# FPGA_14_15.net
KiCad netlist of a schematic drawn in Altium Designer
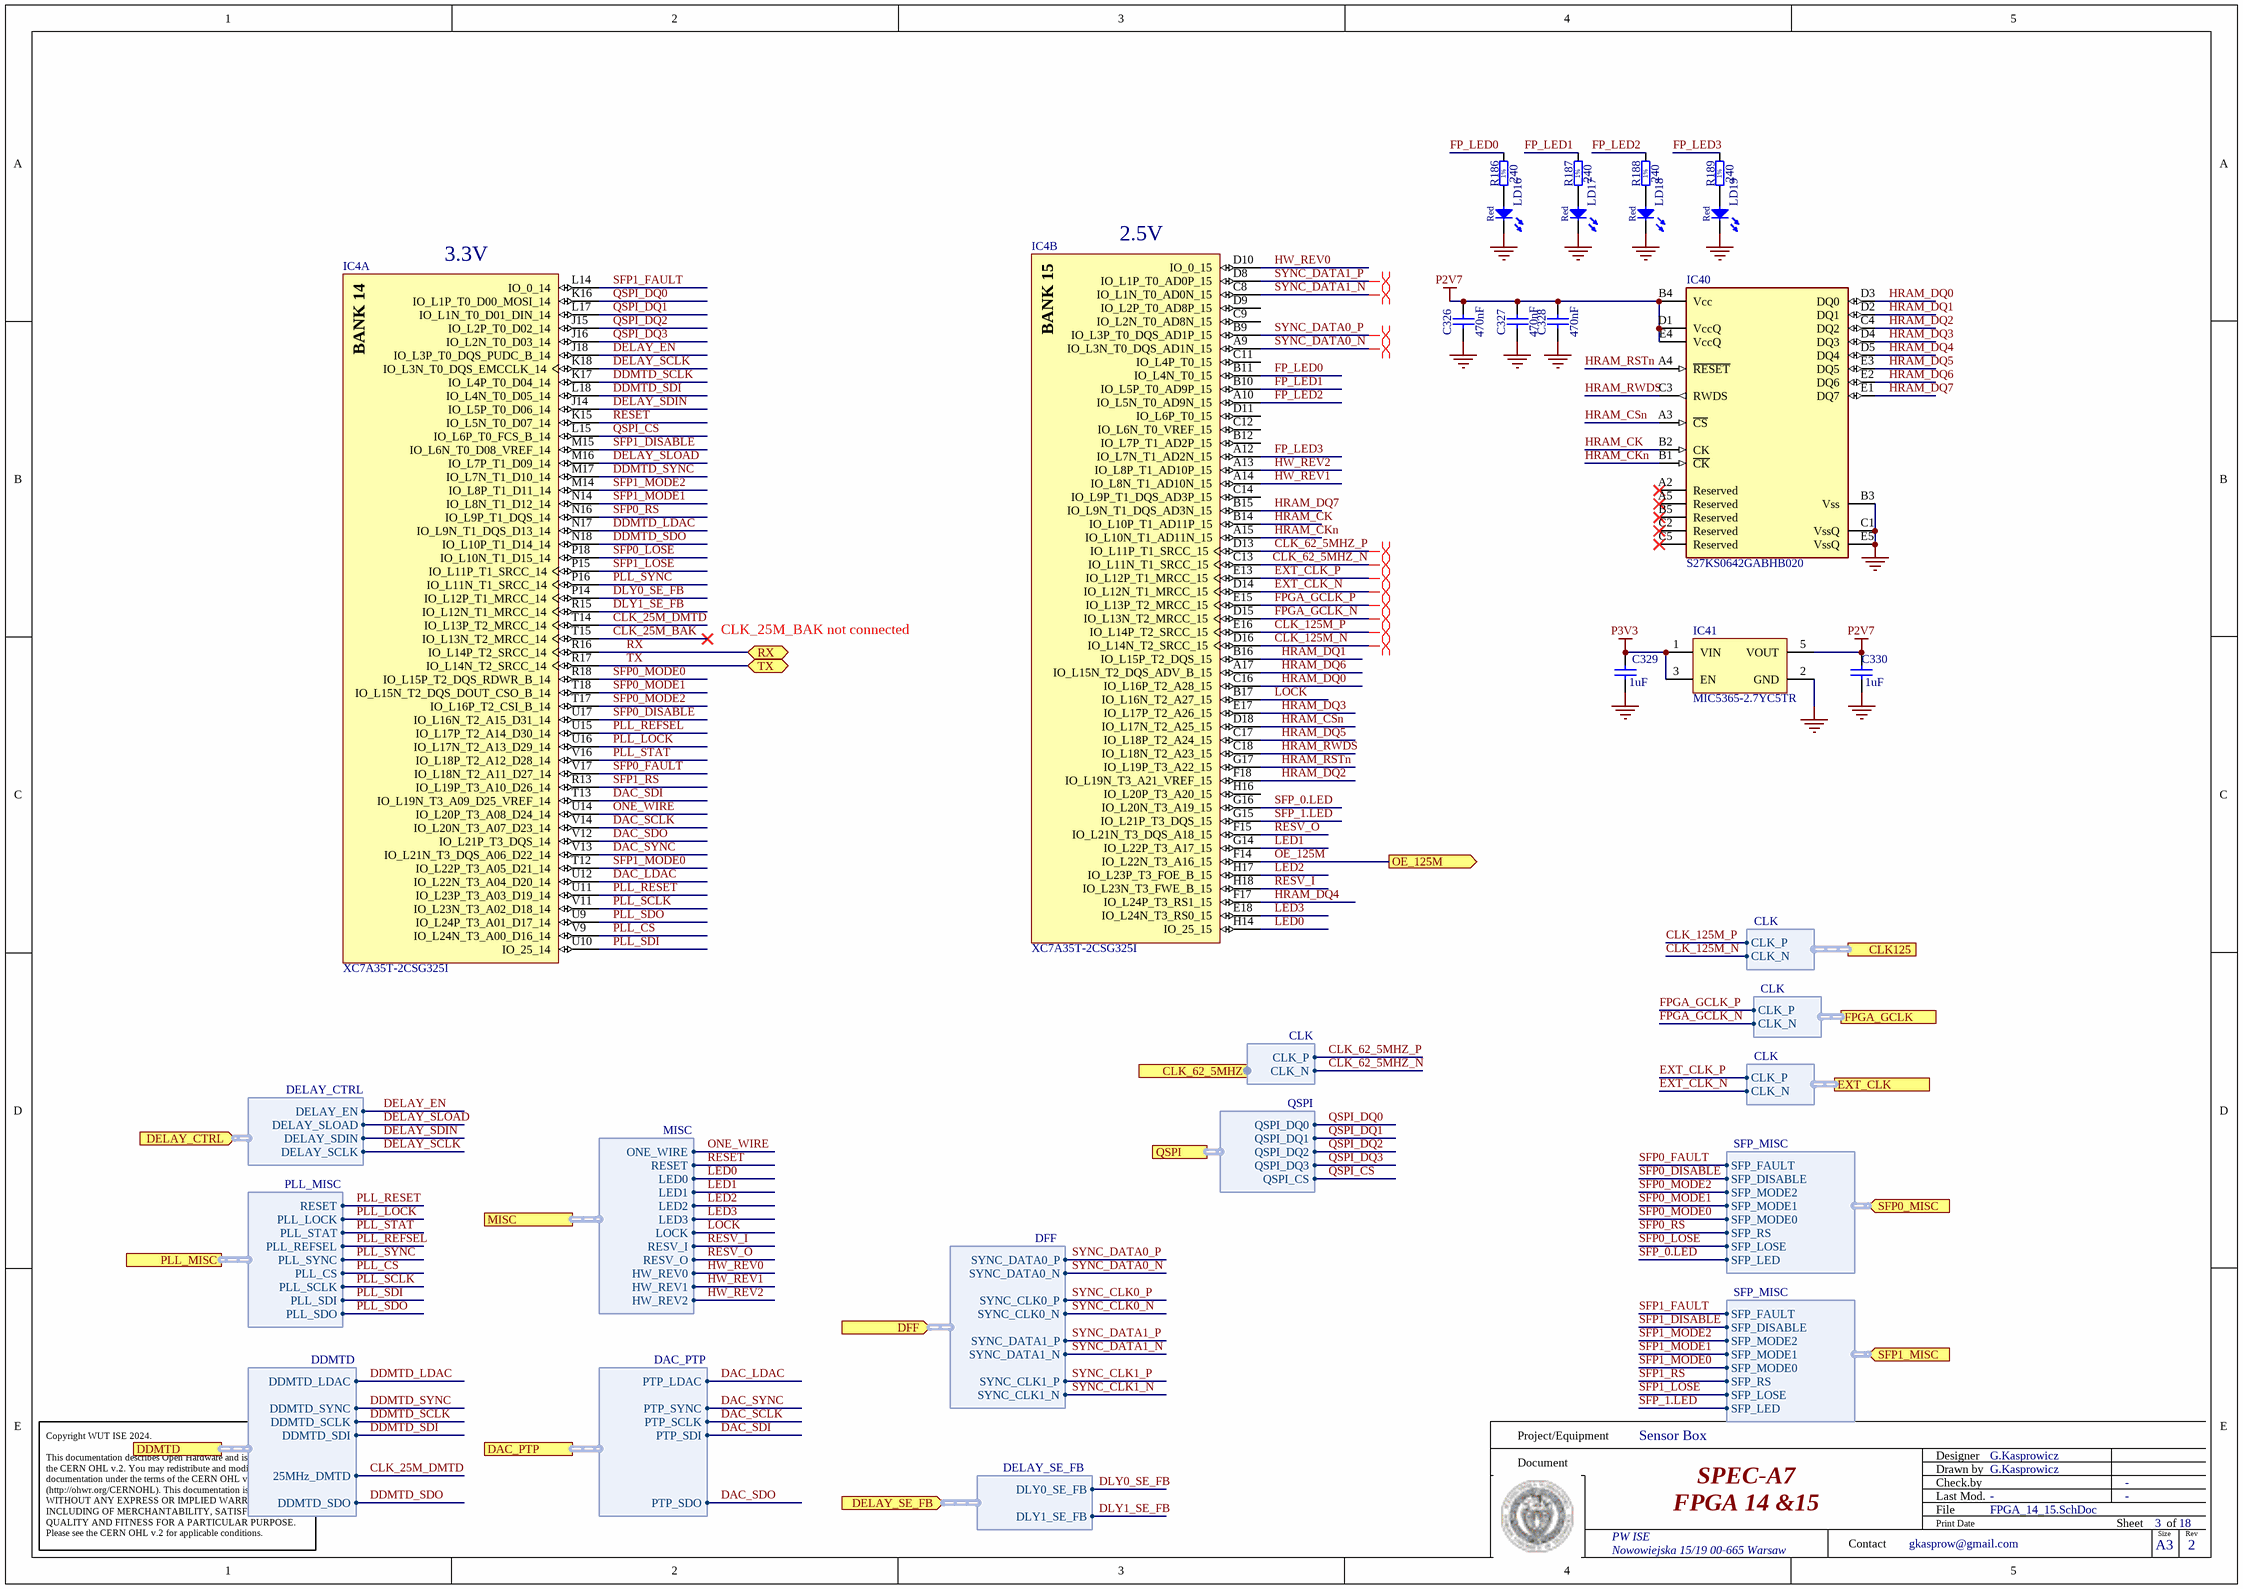
[diagram p0: FPGA_14_15.SchDoc]

(export (version "E")
  (design (tool "Eeschema 10.0.6"))
  (components
    (comp (ref "C326")
      (value "470nF")
      (footprint "CAPC0603X33N")
      (description "Non-polarised capacitor")
      (fields
        (field (name "PART NUMBER") "CC0201_470NF_4V_20%_X5R")
        (field (name "VOLTAGE") "4V")
        (field (name "AUTHOR") "CERN DEM JLC")
      )
      (libsource (lib "Capacitors") (part "Capacitor - non polarized"))
    )
    (comp (ref "C327")
      (value "470nF")
      (footprint "CAPC0603X33N")
      (description "Non-polarised capacitor")
      (fields
        (field (name "PART NUMBER") "CC0201_470NF_4V_20%_X5R")
        (field (name "VOLTAGE") "4V")
        (field (name "AUTHOR") "CERN DEM JLC")
      )
      (libsource (lib "Capacitors") (part "Capacitor - non polarized"))
    )
    (comp (ref "C328")
      (value "470nF")
      (footprint "CAPC0603X33N")
      (description "Non-polarised capacitor")
      (fields
        (field (name "PART NUMBER") "CC0201_470NF_4V_20%_X5R")
        (field (name "VOLTAGE") "4V")
        (field (name "AUTHOR") "CERN DEM JLC")
      )
      (libsource (lib "Capacitors") (part "Capacitor - non polarized"))
    )
    (comp (ref "C329")
      (value "1uF")
      (footprint "CAPC1005X55N")
      (description "Non-polarised capacitor")
      (fields
        (field (name "PART NUMBER") "CC0402_1UF_16V_10%_X5R")
        (field (name "VOLTAGE") "16V")
        (field (name "AUTHOR") "CERN DEM JLC")
      )
      (libsource (lib "Capacitors") (part "Capacitor - non polarized"))
    )
    (comp (ref "C330")
      (value "1uF")
      (footprint "CAPC1005X55N")
      (description "Non-polarised capacitor")
      (fields
        (field (name "PART NUMBER") "CC0402_1UF_16V_10%_X5R")
        (field (name "VOLTAGE") "16V")
        (field (name "AUTHOR") "CERN DEM JLC")
      )
      (libsource (lib "Capacitors") (part "Capacitor - non polarized"))
    )
    (comp (ref "IC4")
      (value "XC7A35T-2CSG325I")
      (footprint "CSG325")
      (description "Artix-7 FPGA, 150 User I/Os, 4 GTP, 324-Ball BGA, Speed Grade 2, Industrial Grade, Pb-Free")
      (fields (field (name "MANUFACTURER") "Xilinx"))
      (libsource (lib "Altium Content Vault") (part "XLNX-XC7A35T-CSG325"))
    )
    (comp (ref "IC40")
      (value "S27KS0642GABHB020")
      (footprint "FP-PG-BGA-24-IPC_A")
      (description "IC PSRAM 64MBIT HYPERBUS 24FBGA")
      (libsource (lib "Altium Content Vault") (part "8dead3f6b3fe1cd27edc2deea5be7c0"))
    )
    (comp (ref "IC41")
      (value "MIC5365-2.7YC5TR")
      (footprint "SOT65P210X110-5N")
      (libsource (lib "MGlib") (part "MIC5365-2.7YC5TR"))
    )
    (comp (ref "LD16")
      (value "Red")
      (footprint "LED_AVAGO_HSMC-C120")
      (description "LED Red 1C 2A")
      (fields
        (field (name "PART NUMBER") "LED_AVAGO_HSMC-C120")
        (field (name "MANUFACTURER") "AVAGO TECHNOLOGIES")
        (field (name "AUTHOR") "CERN DEM JMW")
      )
      (libsource (lib "ICs And Semiconductors") (part "LED Red 1C 2A"))
    )
    (comp (ref "LD17")
      (value "Red")
      (footprint "LED_AVAGO_HSMC-C120")
      (description "LED Red 1C 2A")
      (fields
        (field (name "PART NUMBER") "LED_AVAGO_HSMC-C120")
        (field (name "MANUFACTURER") "AVAGO TECHNOLOGIES")
        (field (name "AUTHOR") "CERN DEM JMW")
      )
      (libsource (lib "ICs And Semiconductors") (part "LED Red 1C 2A"))
    )
    (comp (ref "LD18")
      (value "Red")
      (footprint "LED_AVAGO_HSMC-C120")
      (description "LED Red 1C 2A")
      (fields
        (field (name "PART NUMBER") "LED_AVAGO_HSMC-C120")
        (field (name "MANUFACTURER") "AVAGO TECHNOLOGIES")
        (field (name "AUTHOR") "CERN DEM JMW")
      )
      (libsource (lib "ICs And Semiconductors") (part "LED Red 1C 2A"))
    )
    (comp (ref "LD19")
      (value "Red")
      (footprint "LED_AVAGO_HSMC-C120")
      (description "LED Red 1C 2A")
      (fields
        (field (name "PART NUMBER") "LED_AVAGO_HSMC-C120")
        (field (name "MANUFACTURER") "AVAGO TECHNOLOGIES")
        (field (name "AUTHOR") "CERN DEM JMW")
      )
      (libsource (lib "ICs And Semiconductors") (part "LED Red 1C 2A"))
    )
    (comp (ref "R186")
      (value "240")
      (footprint "RESC1005X40N")
      (description "Resistor - 1%")
      (fields
        (field (name "PART NUMBER") "R0402_240R_1%_0.0625W_100PPM")
        (field (name "POWER") "0.0625W")
        (field (name "AUTHOR") "CERN DEM JLC")
      )
      (libsource (lib "Resistors") (part "Resistor - 1%"))
    )
    (comp (ref "R187")
      (value "240")
      (footprint "RESC1005X40N")
      (description "Resistor - 1%")
      (fields
        (field (name "PART NUMBER") "R0402_240R_1%_0.0625W_100PPM")
        (field (name "POWER") "0.0625W")
        (field (name "AUTHOR") "CERN DEM JLC")
      )
      (libsource (lib "Resistors") (part "Resistor - 1%"))
    )
    (comp (ref "R188")
      (value "240")
      (footprint "RESC1005X40N")
      (description "Resistor - 1%")
      (fields
        (field (name "PART NUMBER") "R0402_240R_1%_0.0625W_100PPM")
        (field (name "POWER") "0.0625W")
        (field (name "AUTHOR") "CERN DEM JLC")
      )
      (libsource (lib "Resistors") (part "Resistor - 1%"))
    )
    (comp (ref "R189")
      (value "240")
      (footprint "RESC1005X40N")
      (description "Resistor - 1%")
      (fields
        (field (name "PART NUMBER") "R0402_240R_1%_0.0625W_100PPM")
        (field (name "POWER") "0.0625W")
        (field (name "AUTHOR") "CERN DEM JLC")
      )
      (libsource (lib "Resistors") (part "Resistor - 1%"))
    )
  )
  (nets
    (net (code "11") (name "/CLK_25M_BAK") (class "Default")
      (node (ref "IC4") (pin "T15") (pinfunction "IO_L13N_T2_MRCC_14_T15") (pintype "bidirectional+no_connect"))
    )
    (net (code "12") (name "/CLK_25M_DMTD") (class "Default")
      (node (ref "IC4") (pin "T14") (pinfunction "IO_L13P_T2_MRCC_14_T14") (pintype "bidirectional"))
    )
    (net (code "13") (name "/CLK_62_5MHZ_N") (class "Default")
      (node (ref "IC4") (pin "C13") (pinfunction "IO_L11N_T1_SRCC_15_C13") (pintype "bidirectional"))
    )
    (net (code "14") (name "/CLK_62_5MHZ_P") (class "Default")
      (node (ref "IC4") (pin "D13") (pinfunction "IO_L11P_T1_SRCC_15_D13") (pintype "bidirectional"))
    )
    (net (code "15") (name "/CLK_125M_N") (class "Default")
      (node (ref "IC4") (pin "D16") (pinfunction "IO_L14N_T2_SRCC_15_D16") (pintype "bidirectional"))
    )
    (net (code "16") (name "/CLK_125M_P") (class "Default")
      (node (ref "IC4") (pin "E16") (pinfunction "IO_L14P_T2_SRCC_15_E16") (pintype "bidirectional"))
    )
    (net (code "17") (name "/DAC_LDAC") (class "Default")
      (node (ref "IC4") (pin "U12") (pinfunction "IO_L22N_T3_A04_D20_14_U12") (pintype "bidirectional"))
    )
    (net (code "18") (name "/DAC_SCLK") (class "Default")
      (node (ref "IC4") (pin "V14") (pinfunction "IO_L20N_T3_A07_D23_14_V14") (pintype "bidirectional"))
    )
    (net (code "19") (name "/DAC_SDI") (class "Default")
      (node (ref "IC4") (pin "T13") (pinfunction "IO_L19N_T3_A09_D25_VREF_14_T13") (pintype "bidirectional"))
    )
    (net (code "20") (name "/DAC_SDO") (class "Default")
      (node (ref "IC4") (pin "V12") (pinfunction "IO_L21P_T3_DQS_14_V12") (pintype "bidirectional"))
    )
    (net (code "21") (name "/DAC_SYNC") (class "Default")
      (node (ref "IC4") (pin "V13") (pinfunction "IO_L21N_T3_DQS_A06_D22_14_V13") (pintype "bidirectional"))
    )
    (net (code "22") (name "/DDMTD_LDAC") (class "Default")
      (node (ref "IC4") (pin "N17") (pinfunction "IO_L9N_T1_DQS_D13_14_N17") (pintype "bidirectional"))
    )
    (net (code "23") (name "/DDMTD_SCLK") (class "Default")
      (node (ref "IC4") (pin "K17") (pinfunction "IO_L4P_T0_D04_14_K17") (pintype "bidirectional"))
    )
    (net (code "24") (name "/DDMTD_SDI") (class "Default")
      (node (ref "IC4") (pin "L18") (pinfunction "IO_L4N_T0_D05_14_L18") (pintype "bidirectional"))
    )
    (net (code "25") (name "/DDMTD_SDO") (class "Default")
      (node (ref "IC4") (pin "N18") (pinfunction "IO_L10P_T1_D14_14_N18") (pintype "bidirectional"))
    )
    (net (code "26") (name "/DDMTD_SYNC") (class "Default")
      (node (ref "IC4") (pin "M17") (pinfunction "IO_L7N_T1_D10_14_M17") (pintype "bidirectional"))
    )
    (net (code "27") (name "/DELAY_EN") (class "Default")
      (node (ref "IC4") (pin "J18") (pinfunction "IO_L3P_T0_DQS_PUDC_B_14_J18") (pintype "bidirectional"))
    )
    (net (code "28") (name "/DELAY_SCLK") (class "Default")
      (node (ref "IC4") (pin "K18") (pinfunction "IO_L3N_T0_DQS_EMCCLK_14_K18") (pintype "bidirectional"))
    )
    (net (code "29") (name "/DELAY_SDIN") (class "Default")
      (node (ref "IC4") (pin "J14") (pinfunction "IO_L5P_T0_D06_14_J14") (pintype "bidirectional"))
    )
    (net (code "30") (name "/DELAY_SLOAD") (class "Default")
      (node (ref "IC4") (pin "M16") (pinfunction "IO_L7P_T1_D09_14_M16") (pintype "bidirectional"))
    )
    (net (code "31") (name "/DLY0_SE_FB") (class "Default")
      (node (ref "IC4") (pin "P14") (pinfunction "IO_L12P_T1_MRCC_14_P14") (pintype "bidirectional"))
    )
    (net (code "32") (name "/DLY1_SE_FB") (class "Default")
      (node (ref "IC4") (pin "R15") (pinfunction "IO_L12N_T1_MRCC_14_R15") (pintype "bidirectional"))
    )
    (net (code "33") (name "/EXT_CLK_N") (class "Default")
      (node (ref "IC4") (pin "D14") (pinfunction "IO_L12N_T1_MRCC_15_D14") (pintype "bidirectional"))
    )
    (net (code "34") (name "/EXT_CLK_P") (class "Default")
      (node (ref "IC4") (pin "E13") (pinfunction "IO_L12P_T1_MRCC_15_E13") (pintype "bidirectional"))
    )
    (net (code "35") (name "/FPGA_GCLK_N") (class "Default")
      (node (ref "IC4") (pin "D15") (pinfunction "IO_L13N_T2_MRCC_15_D15") (pintype "bidirectional"))
    )
    (net (code "36") (name "/FPGA_GCLK_P") (class "Default")
      (node (ref "IC4") (pin "E15") (pinfunction "IO_L13P_T2_MRCC_15_E15") (pintype "bidirectional"))
    )
    (net (code "37") (name "/FP_LED0") (class "Default")
      (node (ref "IC4") (pin "B11") (pinfunction "IO_L4N_T0_15_B11") (pintype "bidirectional"))
      (node (ref "R186") (pin "2") (pinfunction "2_2") (pintype "passive"))
    )
    (net (code "38") (name "/FP_LED1") (class "Default")
      (node (ref "IC4") (pin "B10") (pinfunction "IO_L5P_T0_AD9P_15_B10") (pintype "bidirectional"))
      (node (ref "R187") (pin "2") (pinfunction "2_2") (pintype "passive"))
    )
    (net (code "39") (name "/FP_LED2") (class "Default")
      (node (ref "IC4") (pin "A10") (pinfunction "IO_L5N_T0_AD9N_15_A10") (pintype "bidirectional"))
      (node (ref "R188") (pin "2") (pinfunction "2_2") (pintype "passive"))
    )
    (net (code "40") (name "/FP_LED3") (class "Default")
      (node (ref "IC4") (pin "A12") (pinfunction "IO_L7N_T1_AD2N_15_A12") (pintype "bidirectional"))
      (node (ref "R189") (pin "2") (pinfunction "2_2") (pintype "passive"))
    )
    (net (code "41") (name "/HRAM_CK") (class "Default")
      (node (ref "IC4") (pin "B14") (pinfunction "IO_L10P_T1_AD11P_15_B14") (pintype "bidirectional"))
      (node (ref "IC40") (pin "B2") (pinfunction "CK_B2") (pintype "input"))
    )
    (net (code "42") (name "/HRAM_CKn") (class "Default")
      (node (ref "IC4") (pin "A15") (pinfunction "IO_L10N_T1_AD11N_15_A15") (pintype "bidirectional"))
      (node (ref "IC40") (pin "B1") (pinfunction "~{CK}_B1") (pintype "input"))
    )
    (net (code "43") (name "/HRAM_CSn") (class "Default")
      (node (ref "IC4") (pin "D18") (pinfunction "IO_L17N_T2_A25_15_D18") (pintype "bidirectional"))
      (node (ref "IC40") (pin "A3") (pinfunction "~{CS}_A3") (pintype "input"))
    )
    (net (code "44") (name "/HRAM_DQ0") (class "Default")
      (node (ref "IC4") (pin "C16") (pinfunction "IO_L16P_T2_A28_15_C16") (pintype "bidirectional"))
      (node (ref "IC40") (pin "D3") (pinfunction "DQ0_D3") (pintype "bidirectional"))
    )
    (net (code "45") (name "/HRAM_DQ1") (class "Default")
      (node (ref "IC4") (pin "B16") (pinfunction "IO_L15P_T2_DQS_15_B16") (pintype "bidirectional"))
      (node (ref "IC40") (pin "D2") (pinfunction "DQ1_D2") (pintype "bidirectional"))
    )
    (net (code "46") (name "/HRAM_DQ2") (class "Default")
      (node (ref "IC4") (pin "F18") (pinfunction "IO_L19N_T3_A21_VREF_15_F18") (pintype "bidirectional"))
      (node (ref "IC40") (pin "C4") (pinfunction "DQ2_C4") (pintype "bidirectional"))
    )
    (net (code "47") (name "/HRAM_DQ3") (class "Default")
      (node (ref "IC4") (pin "E17") (pinfunction "IO_L17P_T2_A26_15_E17") (pintype "bidirectional"))
      (node (ref "IC40") (pin "D4") (pinfunction "DQ3_D4") (pintype "bidirectional"))
    )
    (net (code "48") (name "/HRAM_DQ4") (class "Default")
      (node (ref "IC4") (pin "F17") (pinfunction "IO_L24P_T3_RS1_15_F17") (pintype "bidirectional"))
      (node (ref "IC40") (pin "D5") (pinfunction "DQ4_D5") (pintype "bidirectional"))
    )
    (net (code "49") (name "/HRAM_DQ5") (class "Default")
      (node (ref "IC4") (pin "C17") (pinfunction "IO_L18P_T2_A24_15_C17") (pintype "bidirectional"))
      (node (ref "IC40") (pin "E3") (pinfunction "DQ5_E3") (pintype "bidirectional"))
    )
    (net (code "50") (name "/HRAM_DQ6") (class "Default")
      (node (ref "IC4") (pin "A17") (pinfunction "IO_L15N_T2_DQS_ADV_B_15_A17") (pintype "bidirectional"))
      (node (ref "IC40") (pin "E2") (pinfunction "DQ6_E2") (pintype "bidirectional"))
    )
    (net (code "51") (name "/HRAM_DQ7") (class "Default")
      (node (ref "IC4") (pin "B15") (pinfunction "IO_L9N_T1_DQS_AD3N_15_B15") (pintype "bidirectional"))
      (node (ref "IC40") (pin "E1") (pinfunction "DQ7_E1") (pintype "bidirectional"))
    )
    (net (code "52") (name "/HRAM_RSTn") (class "Default")
      (node (ref "IC4") (pin "G17") (pinfunction "IO_L19P_T3_A22_15_G17") (pintype "bidirectional"))
      (node (ref "IC40") (pin "A4") (pinfunction "~{RESET}_A4") (pintype "input"))
    )
    (net (code "53") (name "/HRAM_RWDS") (class "Default")
      (node (ref "IC4") (pin "C18") (pinfunction "IO_L18N_T2_A23_15_C18") (pintype "bidirectional"))
      (node (ref "IC40") (pin "C3") (pinfunction "RWDS_C3") (pintype "output"))
    )
    (net (code "54") (name "/HW_REV0") (class "Default")
      (node (ref "IC4") (pin "D10") (pinfunction "IO_0_15_D10") (pintype "bidirectional"))
    )
    (net (code "55") (name "/HW_REV1") (class "Default")
      (node (ref "IC4") (pin "A14") (pinfunction "IO_L8N_T1_AD10N_15_A14") (pintype "bidirectional"))
    )
    (net (code "56") (name "/HW_REV2") (class "Default")
      (node (ref "IC4") (pin "A13") (pinfunction "IO_L8P_T1_AD10P_15_A13") (pintype "bidirectional"))
    )
    (net (code "57") (name "/LED0") (class "Default")
      (node (ref "IC4") (pin "H14") (pinfunction "IO_25_15_H14") (pintype "bidirectional"))
    )
    (net (code "58") (name "/LED1") (class "Default")
      (node (ref "IC4") (pin "G14") (pinfunction "IO_L22P_T3_A17_15_G14") (pintype "bidirectional"))
    )
    (net (code "59") (name "/LED2") (class "Default")
      (node (ref "IC4") (pin "H17") (pinfunction "IO_L23P_T3_FOE_B_15_H17") (pintype "bidirectional"))
    )
    (net (code "60") (name "/LED3") (class "Default")
      (node (ref "IC4") (pin "E18") (pinfunction "IO_L24N_T3_RS0_15_E18") (pintype "bidirectional"))
    )
    (net (code "61") (name "/LOCK") (class "Default")
      (node (ref "IC4") (pin "B17") (pinfunction "IO_L16N_T2_A27_15_B17") (pintype "bidirectional"))
    )
    (net (code "62") (name "/OE_125M") (class "Default")
      (node (ref "IC4") (pin "F14") (pinfunction "IO_L22N_T3_A16_15_F14") (pintype "bidirectional"))
    )
    (net (code "63") (name "/ONE_WIRE") (class "Default")
      (node (ref "IC4") (pin "U14") (pinfunction "IO_L20P_T3_A08_D24_14_U14") (pintype "bidirectional"))
    )
    (net (code "64") (name "/PLL_CS") (class "Default")
      (node (ref "IC4") (pin "V9") (pinfunction "IO_L24N_T3_A00_D16_14_V9") (pintype "bidirectional"))
    )
    (net (code "65") (name "/PLL_LOCK") (class "Default")
      (node (ref "IC4") (pin "U16") (pinfunction "IO_L17N_T2_A13_D29_14_U16") (pintype "bidirectional"))
    )
    (net (code "66") (name "/PLL_REFSEL") (class "Default")
      (node (ref "IC4") (pin "U15") (pinfunction "IO_L17P_T2_A14_D30_14_U15") (pintype "bidirectional"))
    )
    (net (code "67") (name "/PLL_RESET") (class "Default")
      (node (ref "IC4") (pin "U11") (pinfunction "IO_L23P_T3_A03_D19_14_U11") (pintype "bidirectional"))
    )
    (net (code "68") (name "/PLL_SCLK") (class "Default")
      (node (ref "IC4") (pin "V11") (pinfunction "IO_L23N_T3_A02_D18_14_V11") (pintype "bidirectional"))
    )
    (net (code "69") (name "/PLL_SDI") (class "Default")
      (node (ref "IC4") (pin "U10") (pinfunction "IO_25_14_U10") (pintype "bidirectional"))
    )
    (net (code "70") (name "/PLL_SDO") (class "Default")
      (node (ref "IC4") (pin "U9") (pinfunction "IO_L24P_T3_A01_D17_14_U9") (pintype "bidirectional"))
    )
    (net (code "71") (name "/PLL_STAT") (class "Default")
      (node (ref "IC4") (pin "V16") (pinfunction "IO_L18P_T2_A12_D28_14_V16") (pintype "bidirectional"))
    )
    (net (code "72") (name "/PLL_SYNC") (class "Default")
      (node (ref "IC4") (pin "P16") (pinfunction "IO_L11N_T1_SRCC_14_P16") (pintype "bidirectional"))
    )
    (net (code "73") (name "/QSPI_CS") (class "Default")
      (node (ref "IC4") (pin "L15") (pinfunction "IO_L6P_T0_FCS_B_14_L15") (pintype "bidirectional"))
    )
    (net (code "74") (name "/QSPI_DQ0") (class "Default")
      (node (ref "IC4") (pin "K16") (pinfunction "IO_L1P_T0_D00_MOSI_14_K16") (pintype "bidirectional"))
    )
    (net (code "75") (name "/QSPI_DQ1") (class "Default")
      (node (ref "IC4") (pin "L17") (pinfunction "IO_L1N_T0_D01_DIN_14_L17") (pintype "bidirectional"))
    )
    (net (code "76") (name "/QSPI_DQ2") (class "Default")
      (node (ref "IC4") (pin "J15") (pinfunction "IO_L2P_T0_D02_14_J15") (pintype "bidirectional"))
    )
    (net (code "77") (name "/QSPI_DQ3") (class "Default")
      (node (ref "IC4") (pin "J16") (pinfunction "IO_L2N_T0_D03_14_J16") (pintype "bidirectional"))
    )
    (net (code "78") (name "/RESET") (class "Default")
      (node (ref "IC4") (pin "K15") (pinfunction "IO_L5N_T0_D07_14_K15") (pintype "bidirectional"))
    )
    (net (code "79") (name "/RESV_I") (class "Default")
      (node (ref "IC4") (pin "H18") (pinfunction "IO_L23N_T3_FWE_B_15_H18") (pintype "bidirectional"))
    )
    (net (code "80") (name "/RESV_O") (class "Default")
      (node (ref "IC4") (pin "F15") (pinfunction "IO_L21N_T3_DQS_A18_15_F15") (pintype "bidirectional"))
    )
    (net (code "81") (name "/RX") (class "Default")
      (node (ref "IC4") (pin "R16") (pinfunction "IO_L14P_T2_SRCC_14_R16") (pintype "bidirectional"))
    )
    (net (code "82") (name "/SFP0_DISABLE") (class "Default")
      (node (ref "IC4") (pin "U17") (pinfunction "IO_L16N_T2_A15_D31_14_U17") (pintype "bidirectional"))
    )
    (net (code "83") (name "/SFP0_FAULT") (class "Default")
      (node (ref "IC4") (pin "V17") (pinfunction "IO_L18N_T2_A11_D27_14_V17") (pintype "bidirectional"))
    )
    (net (code "84") (name "/SFP0_LOSE") (class "Default")
      (node (ref "IC4") (pin "P18") (pinfunction "IO_L10N_T1_D15_14_P18") (pintype "bidirectional"))
    )
    (net (code "85") (name "/SFP0_MODE0") (class "Default")
      (node (ref "IC4") (pin "R18") (pinfunction "IO_L15P_T2_DQS_RDWR_B_14_R18") (pintype "bidirectional"))
    )
    (net (code "86") (name "/SFP0_MODE1") (class "Default")
      (node (ref "IC4") (pin "T18") (pinfunction "IO_L15N_T2_DQS_DOUT_CSO_B_14_T18") (pintype "bidirectional"))
    )
    (net (code "87") (name "/SFP0_MODE2") (class "Default")
      (node (ref "IC4") (pin "T17") (pinfunction "IO_L16P_T2_CSI_B_14_T17") (pintype "bidirectional"))
    )
    (net (code "88") (name "/SFP0_RS") (class "Default")
      (node (ref "IC4") (pin "N16") (pinfunction "IO_L9P_T1_DQS_14_N16") (pintype "bidirectional"))
    )
    (net (code "89") (name "/SFP1_DISABLE") (class "Default")
      (node (ref "IC4") (pin "M15") (pinfunction "IO_L6N_T0_D08_VREF_14_M15") (pintype "bidirectional"))
    )
    (net (code "90") (name "/SFP1_FAULT") (class "Default")
      (node (ref "IC4") (pin "L14") (pinfunction "IO_0_14_L14") (pintype "bidirectional"))
    )
    (net (code "91") (name "/SFP1_LOSE") (class "Default")
      (node (ref "IC4") (pin "P15") (pinfunction "IO_L11P_T1_SRCC_14_P15") (pintype "bidirectional"))
    )
    (net (code "92") (name "/SFP1_MODE0") (class "Default")
      (node (ref "IC4") (pin "T12") (pinfunction "IO_L22P_T3_A05_D21_14_T12") (pintype "bidirectional"))
    )
    (net (code "93") (name "/SFP1_MODE1") (class "Default")
      (node (ref "IC4") (pin "N14") (pinfunction "IO_L8N_T1_D12_14_N14") (pintype "bidirectional"))
    )
    (net (code "94") (name "/SFP1_MODE2") (class "Default")
      (node (ref "IC4") (pin "M14") (pinfunction "IO_L8P_T1_D11_14_M14") (pintype "bidirectional"))
    )
    (net (code "95") (name "/SFP1_RS") (class "Default")
      (node (ref "IC4") (pin "R13") (pinfunction "IO_L19P_T3_A10_D26_14_R13") (pintype "bidirectional"))
    )
    (net (code "96") (name "/SFP_0.LED") (class "Default")
      (node (ref "IC4") (pin "G16") (pinfunction "IO_L20N_T3_A19_15_G16") (pintype "bidirectional"))
    )
    (net (code "97") (name "/SFP_1.LED") (class "Default")
      (node (ref "IC4") (pin "G15") (pinfunction "IO_L21P_T3_DQS_15_G15") (pintype "bidirectional"))
    )
    (net (code "102") (name "/SYNC_DATA0_N") (class "Default")
      (node (ref "IC4") (pin "A9") (pinfunction "IO_L3N_T0_DQS_AD1N_15_A9") (pintype "bidirectional"))
    )
    (net (code "103") (name "/SYNC_DATA0_P") (class "Default")
      (node (ref "IC4") (pin "B9") (pinfunction "IO_L3P_T0_DQS_AD1P_15_B9") (pintype "bidirectional"))
    )
    (net (code "104") (name "/SYNC_DATA1_N") (class "Default")
      (node (ref "IC4") (pin "C8") (pinfunction "IO_L1N_T0_AD0N_15_C8") (pintype "bidirectional"))
    )
    (net (code "105") (name "/SYNC_DATA1_P") (class "Default")
      (node (ref "IC4") (pin "D8") (pinfunction "IO_L1P_T0_AD0P_15_D8") (pintype "bidirectional"))
    )
    (net (code "106") (name "/TX") (class "Default")
      (node (ref "IC4") (pin "R17") (pinfunction "IO_L14N_T2_SRCC_14_R17") (pintype "bidirectional"))
    )
    (net (code "117") (name "GND") (class "Default")
      (node (ref "C326") (pin "1") (pinfunction "1_1") (pintype "passive"))
      (node (ref "C327") (pin "1") (pinfunction "1_1") (pintype "passive"))
      (node (ref "C328") (pin "1") (pinfunction "1_1") (pintype "passive"))
      (node (ref "C329") (pin "1") (pinfunction "1_1") (pintype "passive"))
      (node (ref "C330") (pin "1") (pinfunction "1_1") (pintype "passive"))
      (node (ref "IC40") (pin "B3") (pinfunction "Vss_B3") (pintype "power_in"))
      (node (ref "IC40") (pin "C1") (pinfunction "VssQ_C1") (pintype "power_in"))
      (node (ref "IC40") (pin "E5") (pinfunction "VssQ_E5") (pintype "power_in"))
      (node (ref "IC41") (pin "2") (pinfunction "GND_2") (pintype "passive"))
      (node (ref "LD16") (pin "1") (pinfunction "C_1") (pintype "passive"))
      (node (ref "LD17") (pin "1") (pinfunction "C_1") (pintype "passive"))
      (node (ref "LD18") (pin "1") (pinfunction "C_1") (pintype "passive"))
      (node (ref "LD19") (pin "1") (pinfunction "C_1") (pintype "passive"))
    )
    (net (code "118") (name "Net-(LD16-A)") (class "Default")
      (node (ref "LD16") (pin "2") (pinfunction "A_2") (pintype "passive"))
      (node (ref "R186") (pin "1") (pinfunction "1_1") (pintype "passive"))
    )
    (net (code "119") (name "Net-(LD17-A)") (class "Default")
      (node (ref "LD17") (pin "2") (pinfunction "A_2") (pintype "passive"))
      (node (ref "R187") (pin "1") (pinfunction "1_1") (pintype "passive"))
    )
    (net (code "120") (name "Net-(LD18-A)") (class "Default")
      (node (ref "LD18") (pin "2") (pinfunction "A_2") (pintype "passive"))
      (node (ref "R188") (pin "1") (pinfunction "1_1") (pintype "passive"))
    )
    (net (code "121") (name "Net-(LD19-A)") (class "Default")
      (node (ref "LD19") (pin "2") (pinfunction "A_2") (pintype "passive"))
      (node (ref "R189") (pin "1") (pinfunction "1_1") (pintype "passive"))
    )
    (net (code "122") (name "P2V7") (class "Default")
      (node (ref "C326") (pin "2") (pinfunction "2_2") (pintype "passive"))
      (node (ref "C327") (pin "2") (pinfunction "2_2") (pintype "passive"))
      (node (ref "C328") (pin "2") (pinfunction "2_2") (pintype "passive"))
      (node (ref "C330") (pin "2") (pinfunction "2_2") (pintype "passive"))
      (node (ref "IC40") (pin "B4") (pinfunction "Vcc_B4") (pintype "power_in"))
      (node (ref "IC40") (pin "D1") (pinfunction "VccQ_D1") (pintype "power_in"))
      (node (ref "IC40") (pin "E4") (pinfunction "VccQ_E4") (pintype "power_in"))
      (node (ref "IC41") (pin "5") (pinfunction "VOUT_5") (pintype "passive"))
    )
    (net (code "123") (name "P3V3") (class "Default")
      (node (ref "C329") (pin "2") (pinfunction "2_2") (pintype "passive"))
      (node (ref "IC41") (pin "1") (pinfunction "VIN_1") (pintype "passive"))
      (node (ref "IC41") (pin "3") (pinfunction "EN_3") (pintype "passive"))
    )
    (net (code "124") (name "unconnected-(IC4B-IO_L2N_T0_AD8N_15-PadC9)") (class "Default")
      (node (ref "IC4") (pin "C9") (pinfunction "IO_L2N_T0_AD8N_15_C9") (pintype "bidirectional"))
    )
    (net (code "125") (name "unconnected-(IC4B-IO_L2P_T0_AD8P_15-PadD9)") (class "Default")
      (node (ref "IC4") (pin "D9") (pinfunction "IO_L2P_T0_AD8P_15_D9") (pintype "bidirectional"))
    )
    (net (code "126") (name "unconnected-(IC4B-IO_L4P_T0_15-PadC11)") (class "Default")
      (node (ref "IC4") (pin "C11") (pinfunction "IO_L4P_T0_15_C11") (pintype "bidirectional"))
    )
    (net (code "127") (name "unconnected-(IC4B-IO_L6N_T0_VREF_15-PadC12)") (class "Default")
      (node (ref "IC4") (pin "C12") (pinfunction "IO_L6N_T0_VREF_15_C12") (pintype "bidirectional"))
    )
    (net (code "128") (name "unconnected-(IC4B-IO_L6P_T0_15-PadD11)") (class "Default")
      (node (ref "IC4") (pin "D11") (pinfunction "IO_L6P_T0_15_D11") (pintype "bidirectional"))
    )
    (net (code "129") (name "unconnected-(IC4B-IO_L7P_T1_AD2P_15-PadB12)") (class "Default")
      (node (ref "IC4") (pin "B12") (pinfunction "IO_L7P_T1_AD2P_15_B12") (pintype "bidirectional"))
    )
    (net (code "130") (name "unconnected-(IC4B-IO_L9P_T1_DQS_AD3P_15-PadC14)") (class "Default")
      (node (ref "IC4") (pin "C14") (pinfunction "IO_L9P_T1_DQS_AD3P_15_C14") (pintype "bidirectional"))
    )
    (net (code "131") (name "unconnected-(IC4B-IO_L20P_T3_A20_15-PadH16)") (class "Default")
      (node (ref "IC4") (pin "H16") (pinfunction "IO_L20P_T3_A20_15_H16") (pintype "bidirectional"))
    )
    (net (code "132") (name "unconnected-(IC40-Reserved-PadA2)") (class "Default")
      (node (ref "IC40") (pin "A2") (pinfunction "Reserved_A2") (pintype "passive+no_connect"))
    )
    (net (code "133") (name "unconnected-(IC40-Reserved-PadA5)") (class "Default")
      (node (ref "IC40") (pin "A5") (pinfunction "Reserved_A5") (pintype "passive+no_connect"))
    )
    (net (code "134") (name "unconnected-(IC40-Reserved-PadB5)") (class "Default")
      (node (ref "IC40") (pin "B5") (pinfunction "Reserved_B5") (pintype "passive+no_connect"))
    )
    (net (code "135") (name "unconnected-(IC40-Reserved-PadC2)") (class "Default")
      (node (ref "IC40") (pin "C2") (pinfunction "Reserved_C2") (pintype "passive+no_connect"))
    )
    (net (code "136") (name "unconnected-(IC40-Reserved-PadC5)") (class "Default")
      (node (ref "IC40") (pin "C5") (pinfunction "Reserved_C5") (pintype "passive+no_connect"))
    )
  )
)
